# DB_Power-X01.net
KiCad netlist of a schematic drawn in Altium Designer
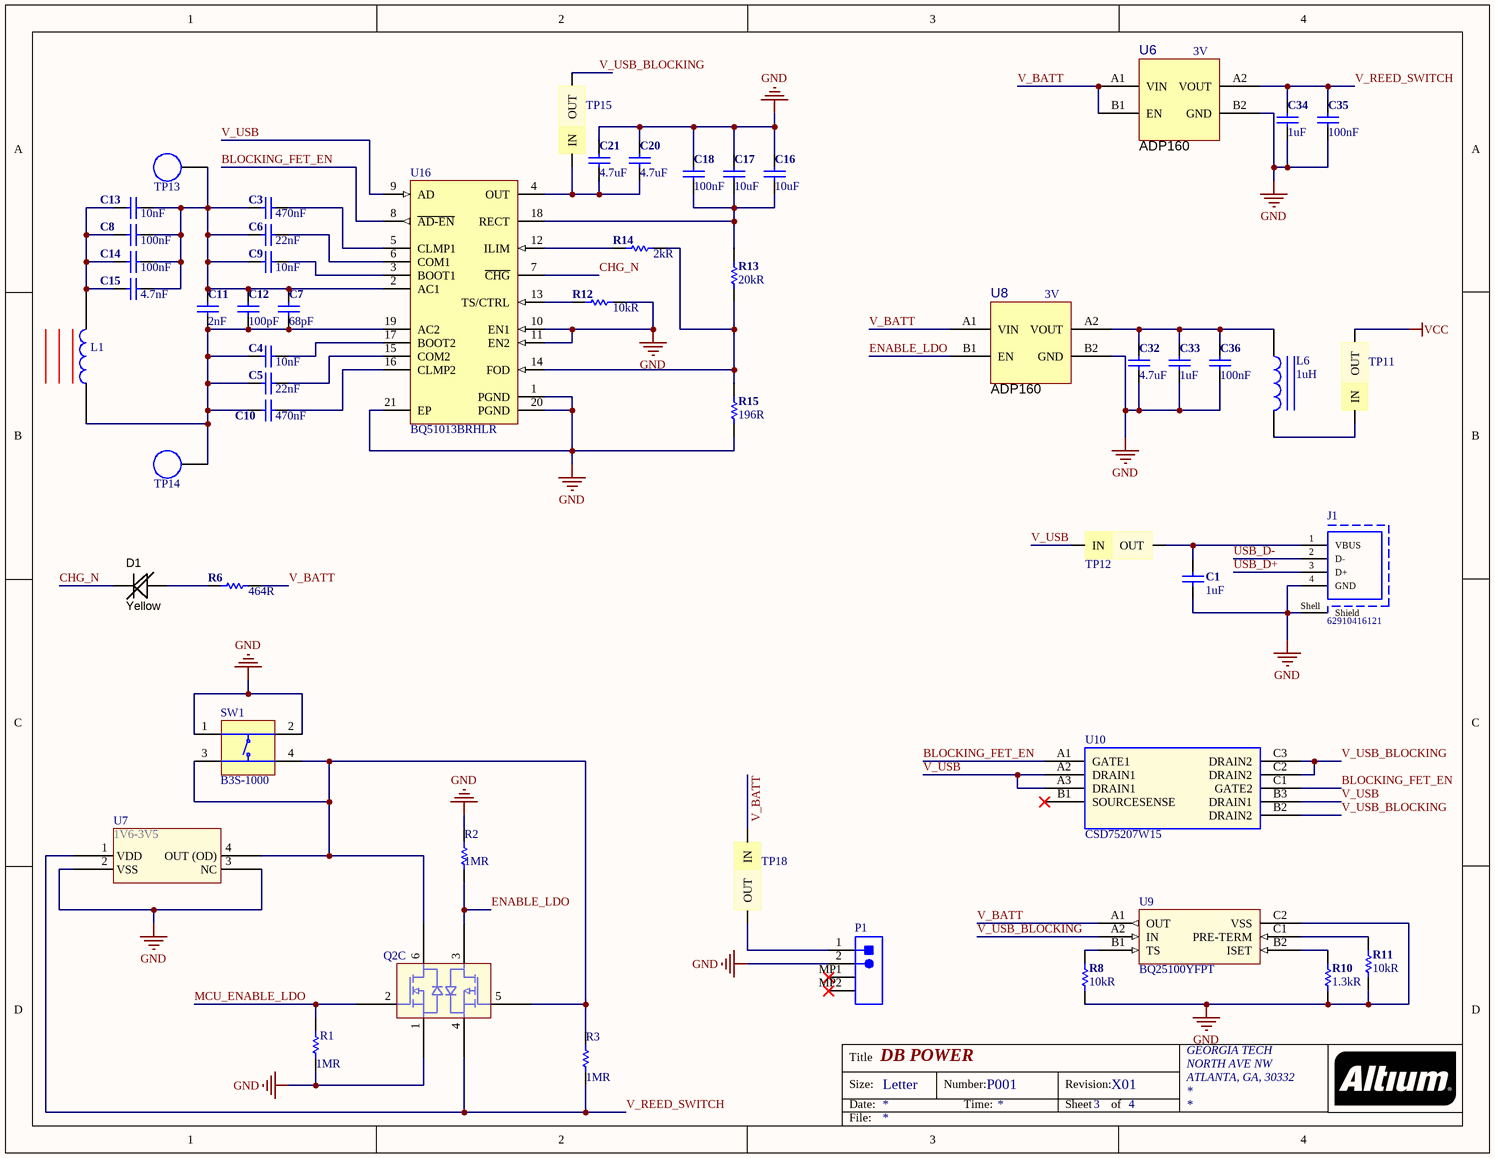
[diagram p0: DB_Power-X01.SchDoc]

(export (version "E")
  (design (tool "Eeschema 10.0.6"))
  (components
    (comp (ref "C1")
      (value "1uF")
      (footprint "C0402")
      (fields
        (field (name "MANUFACTURER") "Yageo")
        (field (name "MANUFACTURER PART NUMBER") "CC0402MRX5R5BB105")
        (field (name "TOLERANCE") "20%")
      )
      (libsource (lib "DB-X01") (part "C-0402(1005)"))
    )
    (comp (ref "C3")
      (value "470nF")
      (footprint "C0402")
      (fields
        (field (name "MANUFACTURER") "Murata")
        (field (name "MANUFACTURER PART NUMBER") "GRT155R61E474ME01D")
        (field (name "TOLERANCE") "20%")
      )
      (libsource (lib "DB-X01") (part "C-0402(1005)"))
    )
    (comp (ref "C4")
      (value "10nF")
      (footprint "C0402")
      (fields
        (field (name "MANUFACTURER") "KEMET")
        (field (name "MANUFACTURER PART NUMBER") "C0402C103J3RACTU")
        (field (name "TOLERANCE") "5%")
      )
      (libsource (lib "DB-X01") (part "C-0402(1005)"))
    )
    (comp (ref "C5")
      (value "22nF")
      (footprint "C0402")
      (fields
        (field (name "MANUFACTURER") "Murata")
        (field (name "MANUFACTURER PART NUMBER") "GRM155R71E223KA61D")
        (field (name "TOLERANCE") "10%")
      )
      (libsource (lib "DB-X01") (part "C-0402(1005)"))
    )
    (comp (ref "C6")
      (value "22nF")
      (footprint "C0402")
      (fields
        (field (name "MANUFACTURER") "Murata")
        (field (name "MANUFACTURER PART NUMBER") "GRM155R71E223KA61D")
        (field (name "TOLERANCE") "10%")
      )
      (libsource (lib "DB-X01") (part "C-0402(1005)"))
    )
    (comp (ref "C7")
      (value "68pF")
      (footprint "C0402")
      (fields
        (field (name "MANUFACTURER") "KEMET")
        (field (name "MANUFACTURER PART NUMBER") "CBR04C680F3GAC")
        (field (name "TOLERANCE") "1%")
      )
      (libsource (lib "DB-X01") (part "C-0402(1005)"))
    )
    (comp (ref "C8")
      (value "100nF")
      (footprint "C0402")
      (fields
        (field (name "MANUFACTURER") "Taiyo Yuden")
        (field (name "MANUFACTURER PART NUMBER") "TMK105BJ104KV-F")
        (field (name "TOLERANCE") "10%")
      )
      (libsource (lib "DB-X01") (part "C-0402(1005)"))
    )
    (comp (ref "C9")
      (value "10nF")
      (footprint "C0402")
      (fields
        (field (name "MANUFACTURER") "KEMET")
        (field (name "MANUFACTURER PART NUMBER") "C0402C103J3RACTU")
        (field (name "TOLERANCE") "5%")
      )
      (libsource (lib "DB-X01") (part "C-0402(1005)"))
    )
    (comp (ref "C10")
      (value "470nF")
      (footprint "C0402")
      (fields
        (field (name "MANUFACTURER") "Murata")
        (field (name "MANUFACTURER PART NUMBER") "GRT155R61E474ME01D")
        (field (name "TOLERANCE") "20%")
      )
      (libsource (lib "DB-X01") (part "C-0402(1005)"))
    )
    (comp (ref "C11")
      (value "2nF")
      (footprint "C0402")
      (fields
        (field (name "MANUFACTURER") "KEMET")
        (field (name "MANUFACTURER PART NUMBER") "C0402C202J3GACTU")
        (field (name "TOLERANCE") "5%")
      )
      (libsource (lib "DB-X01") (part "C-0402(1005)"))
    )
    (comp (ref "C12")
      (value "100pF")
      (footprint "C0402")
      (fields
        (field (name "MANUFACTURER") "KEMET")
        (field (name "MANUFACTURER PART NUMBER") "CBR04C101F3GAC")
        (field (name "TOLERANCE") "1%")
      )
      (libsource (lib "DB-X01") (part "C-0402(1005)"))
    )
    (comp (ref "C13")
      (value "10nF")
      (footprint "C0402")
      (fields
        (field (name "MANUFACTURER") "Yageo")
        (field (name "MANUFACTURER PART NUMBER") "CC0402JRX7R8BB103")
        (field (name "TOLERANCE") "5%")
      )
      (libsource (lib "DB-X01") (part "C-0402(1005)"))
    )
    (comp (ref "C14")
      (value "100nF")
      (footprint "C0402")
      (fields
        (field (name "MANUFACTURER") "Taiyo Yuden")
        (field (name "MANUFACTURER PART NUMBER") "TMK105BJ104KV-F")
        (field (name "TOLERANCE") "10%")
      )
      (libsource (lib "DB-X01") (part "C-0402(1005)"))
    )
    (comp (ref "C15")
      (value "4.7nF")
      (footprint "C0402")
      (fields
        (field (name "MANUFACTURER") "Yageo")
        (field (name "MANUFACTURER PART NUMBER") "CC0402JRX7R8BB472")
        (field (name "TOLERANCE") "5%")
      )
      (libsource (lib "DB-X01") (part "C-0402(1005)"))
    )
    (comp (ref "C16")
      (value "10uF")
      (footprint "C0603")
      (fields
        (field (name "MANUFACTURER") "Murata")
        (field (name "MANUFACTURER PART NUMBER") "GRM188R61E106MA73J")
        (field (name "TOLERANCE") "20%")
      )
      (libsource (lib "DB-X01") (part "C-0603(1608)"))
    )
    (comp (ref "C17")
      (value "10uF")
      (footprint "C0603")
      (fields
        (field (name "MANUFACTURER") "Murata")
        (field (name "MANUFACTURER PART NUMBER") "GRM188R61E106MA73J")
        (field (name "TOLERANCE") "20%")
      )
      (libsource (lib "DB-X01") (part "C-0603(1608)"))
    )
    (comp (ref "C18")
      (value "100nF")
      (footprint "C0603")
      (fields
        (field (name "MANUFACTURER") "Yageo")
        (field (name "MANUFACTURER PART NUMBER") "CC0402ZRY5V8BB104")
        (field (name "TOLERANCE") "80%")
      )
      (libsource (lib "DB-X01") (part "C-0603(1608)"))
    )
    (comp (ref "C20")
      (value "4.7uF")
      (footprint "C0402")
      (description "0402 10 V 4.7 uF ±20% Tolerance X5R Multilayer Ceramic Chip Capacitor")
      (fields
        (field (name "MANUFACTURER") "Murata")
        (field (name "MANUFACTURER PART NUMBER") "GRM155R61A475MEAAD")
      )
      (libsource (lib "DB-X01") (part "C-0402(1005)"))
    )
    (comp (ref "C21")
      (value "4.7uF")
      (footprint "C0402")
      (description "0402 10 V 4.7 uF ±20% Tolerance X5R Multilayer Ceramic Chip Capacitor")
      (fields
        (field (name "MANUFACTURER") "Murata")
        (field (name "MANUFACTURER PART NUMBER") "GRM155R61A475MEAAD")
      )
      (libsource (lib "DB-X01") (part "C-0402(1005)"))
    )
    (comp (ref "C32")
      (value "4.7uF")
      (footprint "C0402")
      (description "0402 10 V 4.7 uF ±20% Tolerance X5R Multilayer Ceramic Chip Capacitor")
      (fields
        (field (name "MANUFACTURER") "Murata")
        (field (name "MANUFACTURER PART NUMBER") "GRM155R61A475MEAAD")
      )
      (libsource (lib "DB-X01") (part "C-0402(1005)"))
    )
    (comp (ref "C33")
      (value "1uF")
      (footprint "C0402")
      (fields
        (field (name "MANUFACTURER") "Yageo")
        (field (name "MANUFACTURER PART NUMBER") "CC0402MRX5R5BB105")
        (field (name "TOLERANCE") "20%")
      )
      (libsource (lib "DB-X01") (part "C-0402(1005)"))
    )
    (comp (ref "C34")
      (value "1uF")
      (footprint "C0402")
      (fields
        (field (name "MANUFACTURER") "Yageo")
        (field (name "MANUFACTURER PART NUMBER") "CC0402MRX5R5BB105")
        (field (name "TOLERANCE") "20%")
      )
      (libsource (lib "DB-X01") (part "C-0402(1005)"))
    )
    (comp (ref "C35")
      (value "100nF")
      (footprint "C0402")
      (fields
        (field (name "MANUFACTURER") "Taiyo Yuden")
        (field (name "MANUFACTURER PART NUMBER") "TMK105BJ104KV-F")
        (field (name "TOLERANCE") "10%")
      )
      (libsource (lib "DB-X01") (part "C-0402(1005)"))
    )
    (comp (ref "C36")
      (value "100nF")
      (footprint "C0402")
      (fields
        (field (name "MANUFACTURER") "Taiyo Yuden")
        (field (name "MANUFACTURER PART NUMBER") "TMK105BJ104KV-F")
        (field (name "TOLERANCE") "10%")
      )
      (libsource (lib "DB-X01") (part "C-0402(1005)"))
    )
    (comp (ref "D1")
      (value "Yellow")
      (footprint "LED_0402")
      (description "Single Color LED, Super Bright Yellow, Water Clear, 0.8mm")
      (fields
        (field (name "MANUFACTURER") "Kingbright")
        (field (name "MANUFACTURER PART NUMBER") "APHHS1005SYCK")
      )
      (libsource (lib "DB-X01") (part "LED_0402(1005)"))
    )
    (comp (ref "J1")
      (value "62910416121")
      (footprint "62910416121")
      (description "USB 2.0 Type B Receptacle WR-COM, Horizontal, SMT, with Pads and Pegs")
      (fields (field (name "MANUFACTURER") "Wurth Electronics"))
      (libsource (lib "Altium Content Vault") (part "WE-USB-4-1SHLD"))
    )
    (comp (ref "L1")
      (value "WIRELESS CHARGING COIL, RECEIVER")
      (footprint "760308101219")
      (description "General Purpose Inductor, 11.8uH, 10%, 1 Element")
      (fields
        (field (name "MANUFACTURER") "Wurth Electronics")
        (field (name "MANUFACTURER PART NUMBER") "760308101219")
      )
      (libsource (lib "DB-X01") (part "WIRELESS_CHARGING_COIL"))
    )
    (comp (ref "L6")
      (value "1uH")
      (footprint "L0402")
      (description "General Purpose Inductor, 1uH, 20%, 1 Element, Ferrite-Core, SMD, 0402")
      (fields
        (field (name "MANUFACTURER") "TDK")
        (field (name "MANUFACTURER PART NUMBER") "MLZ1005M1R0WT000")
      )
      (libsource (lib "DB-X01") (part "Inductor Iron"))
    )
    (comp (ref "P1")
      (value "B2B-PH-SM4-TB(LF)(SN)")
      (footprint "JST-B2B-PH-SM4-TB-2_V")
      (description "Male Header, Pitch 2 mm, 1 x 2 Position, Height 6.6 mm, RoHS, Tape and Reel")
      (fields (field (name "MANUFACTURER") "JST"))
      (libsource (lib "Altium Content Vault") (part "CN-1P-2M-R2"))
    )
    (comp (ref "Q2")
      (value "dual fet SSMini6")
      (footprint "SSMini6-F3-B")
      (fields
        (field (name "MANUFACTURER") "Panasonic")
        (field (name "MANUFACTURER PART NUMBER") "FG6943010R")
      )
      (libsource (lib "DB-X01") (part "FG6943010R"))
    )
    (comp (ref "R1")
      (value "AC0402FR-071ML")
      (footprint "RESC1005X37X25LL05T10")
      (description "100 ohm resistor")
      (fields
        (field (name "MANUFACTURER") "Yageo")
        (field (name "RESISTANCE") "1MR")
        (field (name "TOLERANCE") "1%")
      )
      (libsource (lib "Altium Content Vault") (part "RES"))
    )
    (comp (ref "R2")
      (value "AC0402FR-071ML")
      (footprint "RESC1005X37X25LL05T10")
      (description "100 ohm resistor")
      (fields
        (field (name "MANUFACTURER") "Yageo")
        (field (name "RESISTANCE") "1MR")
        (field (name "TOLERANCE") "1%")
      )
      (libsource (lib "Altium Content Vault") (part "RES"))
    )
    (comp (ref "R3")
      (value "AC0402FR-071ML")
      (footprint "RESC1005X37X25LL05T10")
      (description "100 ohm resistor")
      (fields
        (field (name "MANUFACTURER") "Yageo")
        (field (name "RESISTANCE") "1MR")
        (field (name "TOLERANCE") "1%")
      )
      (libsource (lib "Altium Content Vault") (part "RES"))
    )
    (comp (ref "R6")
      (value "464R")
      (footprint "R0402")
      (fields
        (field (name "MANUFACTURER") "Yageo")
        (field (name "MANUFACTURER PART NUMBER") "RC0402FR-07464RL")
        (field (name "TOLERANCE") "1%")
      )
      (libsource (lib "DB-X01") (part "R-0402(1005)"))
    )
    (comp (ref "R8")
      (value "10kR")
      (footprint "R0402")
      (fields
        (field (name "MANUFACTURER") "Yageo")
        (field (name "MANUFACTURER PART NUMBER") "AC0402FR-0710KL")
        (field (name "TOLERANCE") "1%")
      )
      (libsource (lib "DB-X01") (part "R-0402(1005)"))
    )
    (comp (ref "R10")
      (value "1.3kR")
      (footprint "R0402")
      (fields
        (field (name "MANUFACTURER") "Yageo")
        (field (name "MANUFACTURER PART NUMBER") "RC0402FR-071K3L")
        (field (name "TOLERANCE") "1%")
      )
      (libsource (lib "DB-X01") (part "R-0402(1005)"))
    )
    (comp (ref "R11")
      (value "10kR")
      (footprint "R0402")
      (fields
        (field (name "MANUFACTURER") "Yageo")
        (field (name "MANUFACTURER PART NUMBER") "AC0402FR-0710KL")
        (field (name "TOLERANCE") "1%")
      )
      (libsource (lib "DB-X01") (part "R-0402(1005)"))
    )
    (comp (ref "R12")
      (value "10kR")
      (footprint "R0402")
      (fields
        (field (name "MANUFACTURER") "Yageo")
        (field (name "MANUFACTURER PART NUMBER") "AC0402FR-0710KL")
        (field (name "TOLERANCE") "1%")
      )
      (libsource (lib "DB-X01") (part "R-0402(1005)"))
    )
    (comp (ref "R13")
      (value "20kR")
      (footprint "R0402")
      (fields
        (field (name "MANUFACTURER") "Yageo")
        (field (name "MANUFACTURER PART NUMBER") "AC0402FR-0720KL")
        (field (name "TOLERANCE") "1%")
      )
      (libsource (lib "DB-X01") (part "R-0402(1005)"))
    )
    (comp (ref "R14")
      (value "2kR")
      (footprint "R0402")
      (fields
        (field (name "MANUFACTURER") "Yageo")
        (field (name "MANUFACTURER PART NUMBER") "AC0402FR-072KL")
        (field (name "TOLERANCE") "1%")
      )
      (libsource (lib "DB-X01") (part "R-0402(1005)"))
    )
    (comp (ref "R15")
      (value "196R")
      (footprint "R0402")
      (fields
        (field (name "MANUFACTURER") "Vishay")
        (field (name "MANUFACTURER PART NUMBER") "CRCW0402196RFKED")
        (field (name "TOLERANCE") "1%")
      )
      (libsource (lib "DB-X01") (part "R-0402(1005)"))
    )
    (comp (ref "SW1")
      (value "B3S-1000")
      (footprint "OMRON-B3S-1000-4_V")
      (description "Sealed Tactile Switch, SPST-NO, 3 to 24 V, -25 to 70 degC, 4-Pin SMD, RoHS, Bulk")
      (fields (field (name "MANUFACTURER") "Omron") (field (name "MANUFACTURER PART NUMBER") "B3S-1000P"))
      (libsource (lib "Altium Content Vault") (part "SW-SPST-4_A"))
    )
    (comp (ref "TP11")
      (value "JUMPER")
      (footprint "JUMPER")
      (description "SHUNT LP W/HANDLE 2 POS 30AU")
      (fields
        (field (name "MANUFACTURER") "TE Connectivity")
        (field (name "MANUFACTURER PART NUMBER") "8815452")
      )
      (libsource (lib "DB-X01") (part "JUMPER"))
    )
    (comp (ref "TP12")
      (value "JUMPER")
      (footprint "JUMPER")
      (description "SHUNT LP W/HANDLE 2 POS 30AU")
      (fields
        (field (name "MANUFACTURER") "TE Connectivity")
        (field (name "MANUFACTURER PART NUMBER") "8815452")
      )
      (libsource (lib "") (part "JUMPER_2"))
    )
    (comp (ref "TP13")
      (value "S1751-46R")
      (footprint "S1751-46R")
      (description "PC TEST POINT TIN SMD")
      (fields (field (name "MANUFACTURER") "Harwin Inc."))
      (libsource (lib "DB-X01") (part "S1751-46R"))
    )
    (comp (ref "TP14")
      (value "S1751-46R")
      (footprint "S1751-46R")
      (description "PC TEST POINT TIN SMD")
      (fields (field (name "MANUFACTURER") "Harwin Inc."))
      (libsource (lib "DB-X01") (part "S1751-46R"))
    )
    (comp (ref "TP15")
      (value "JUMPER")
      (footprint "JUMPER")
      (description "SHUNT LP W/HANDLE 2 POS 30AU")
      (fields
        (field (name "MANUFACTURER") "TE Connectivity")
        (field (name "MANUFACTURER PART NUMBER") "8815452")
      )
      (libsource (lib "DB-X01") (part "JUMPER"))
    )
    (comp (ref "TP18")
      (value "JUMPER")
      (footprint "JUMPER")
      (description "SHUNT LP W/HANDLE 2 POS 30AU")
      (fields
        (field (name "MANUFACTURER") "TE Connectivity")
        (field (name "MANUFACTURER PART NUMBER") "8815452")
      )
      (libsource (lib "") (part "JUMPER_1"))
    )
    (comp (ref "U6")
      (value "ADP160")
      (footprint "ADP160")
      (description "Fixed Positive LDO Regulator, 3V, 0.1V Dropout, CMOS, PBGA4")
      (fields
        (field (name "MANUFACTURER") "Analog Devices")
        (field (name "MANUFACTURER PART NUMBER") "ADP172ACBZ-3.0-R7")
        (field (name "OUTPUT VOLTAGE") "3V")
      )
      (libsource (lib "DB-X01") (part "ADP160"))
    )
    (comp (ref "U7")
      (value "S-5712ANSL2-I4T1U")
      (footprint "SNT-4A")
      (description "MAGNETIC SWITCH UNIPOLAR SNT-4A")
      (fields (field (name "MANUFACTURER") "ABLIC U.S.A."))
      (libsource (lib "DB-X01") (part "S-5712ANSL2-I4T1U"))
    )
    (comp (ref "U8")
      (value "ADP160")
      (footprint "ADP160")
      (description "Fixed Positive LDO Regulator, 3V, 0.1V Dropout, CMOS, PBGA4")
      (fields
        (field (name "MANUFACTURER") "Analog Devices")
        (field (name "MANUFACTURER PART NUMBER") "ADP172ACBZ-3.0-R7")
        (field (name "OUTPUT VOLTAGE") "3V")
      )
      (libsource (lib "DB-X01") (part "ADP160"))
    )
    (comp (ref "U9")
      (value "BQ25100YFPT")
      (footprint "YZP0006")
      (description "Power Supply Support Circuit")
      (fields (field (name "MANUFACTURER") "Texas Instruments"))
      (libsource (lib "DB-X01") (part "BQ25100YFPT"))
    )
    (comp (ref "U10")
      (value "CSD75207W15")
      (footprint "YZF0009")
      (description "Small Signal Field-Effect Transistor, P-Channel, Metal-oxide Semiconductor FET")
      (fields (field (name "MANUFACTURER") "Texas Instruments"))
      (libsource (lib "DB-X01") (part "CSD75207W15"))
    )
    (comp (ref "U16")
      (value "BQ51013BRHLR")
      (footprint "BQ51013BRHLR")
      (fields (field (name "MANUFACTURER") "Texas Instruments"))
      (libsource (lib "DB-X01") (part "TI-BQ51013B-RHL20"))
    )
  )
  (nets
    (net (code "1") (name "/BLOCKING_FET_EN") (class "Default")
      (node (ref "U10") (pin "A1") (pinfunction "GATE1_A1") (pintype "passive"))
      (node (ref "U10") (pin "C1") (pinfunction "GATE2_C1") (pintype "passive"))
      (node (ref "U16") (pin "8") (pinfunction "~{AD-EN}_8") (pintype "output"))
    )
    (net (code "2") (name "/CHG_N") (class "Default")
      (node (ref "D1") (pin "K") (pinfunction "K_K") (pintype "passive"))
      (node (ref "U16") (pin "7") (pinfunction "~{CHG}_7") (pintype "open_collector"))
    )
    (net (code "3") (name "/ENABLE_LDO") (class "Default")
      (node (ref "Q2") (pin "3") (pinfunction "D_3") (pintype "passive"))
      (node (ref "R2") (pin "1") (pinfunction "1_1") (pintype "passive"))
      (node (ref "U8") (pin "B1") (pinfunction "EN_B1") (pintype "passive"))
    )
    (net (code "4") (name "/MCU_ENABLE_LDO") (class "Default")
      (node (ref "Q2") (pin "2") (pinfunction "G_2") (pintype "passive"))
      (node (ref "R1") (pin "1") (pinfunction "1_1") (pintype "passive"))
    )
    (net (code "5") (name "/USB_D+") (class "Default")
      (node (ref "J1") (pin "3") (pinfunction "D+_3") (pintype "passive"))
    )
    (net (code "6") (name "/USB_D-") (class "Default")
      (node (ref "J1") (pin "2") (pinfunction "D-_2") (pintype "passive"))
    )
    (net (code "7") (name "/V_BATT") (class "Default")
      (node (ref "R6") (pin "2") (pinfunction "2_2") (pintype "passive"))
      (node (ref "TP18") (pin "1") (pinfunction "IN_1") (pintype "passive"))
      (node (ref "U6") (pin "A1") (pinfunction "VIN_A1") (pintype "passive"))
      (node (ref "U6") (pin "B1") (pinfunction "EN_B1") (pintype "passive"))
      (node (ref "U8") (pin "A1") (pinfunction "VIN_A1") (pintype "passive"))
      (node (ref "U9") (pin "A1") (pinfunction "OUT_A1") (pintype "output"))
    )
    (net (code "8") (name "/V_REED_SWITCH") (class "Default")
      (node (ref "C34") (pin "1") (pinfunction "1_1") (pintype "passive"))
      (node (ref "C35") (pin "2") (pinfunction "2_2") (pintype "passive"))
      (node (ref "Q2") (pin "4") (pinfunction "S_4") (pintype "passive"))
      (node (ref "R3") (pin "1") (pinfunction "1_1") (pintype "passive"))
      (node (ref "U6") (pin "A2") (pinfunction "VOUT_A2") (pintype "passive"))
      (node (ref "U7") (pin "1") (pinfunction "VDD_1") (pintype "passive"))
    )
    (net (code "9") (name "/V_USB") (class "Default")
      (node (ref "TP12") (pin "1") (pinfunction "IN_1") (pintype "passive"))
      (node (ref "U10") (pin "A2") (pinfunction "DRAIN1_A2") (pintype "passive"))
      (node (ref "U10") (pin "A3") (pinfunction "DRAIN1_A3") (pintype "passive"))
      (node (ref "U10") (pin "B3") (pinfunction "DRAIN1_B3") (pintype "passive"))
      (node (ref "U16") (pin "9") (pinfunction "AD_9") (pintype "input"))
    )
    (net (code "10") (name "/V_USB_BLOCKING") (class "Default")
      (node (ref "TP15") (pin "2") (pinfunction "OUT_2") (pintype "passive"))
      (node (ref "U10") (pin "B2") (pinfunction "DRAIN2_B2") (pintype "passive"))
      (node (ref "U10") (pin "C2") (pinfunction "DRAIN2_C2") (pintype "passive"))
      (node (ref "U10") (pin "C3") (pinfunction "DRAIN2_C3") (pintype "passive"))
      (node (ref "U9") (pin "A2") (pinfunction "IN_A2") (pintype "input"))
    )
    (net (code "11") (name "GND") (class "Default")
      (node (ref "C1") (pin "2") (pinfunction "2_2") (pintype "passive"))
      (node (ref "C16") (pin "2") (pinfunction "2_2") (pintype "passive"))
      (node (ref "C17") (pin "2") (pinfunction "2_2") (pintype "passive"))
      (node (ref "C18") (pin "2") (pinfunction "2_2") (pintype "passive"))
      (node (ref "C20") (pin "1") (pinfunction "1_1") (pintype "passive"))
      (node (ref "C21") (pin "1") (pinfunction "1_1") (pintype "passive"))
      (node (ref "C32") (pin "2") (pinfunction "2_2") (pintype "passive"))
      (node (ref "C33") (pin "2") (pinfunction "2_2") (pintype "passive"))
      (node (ref "C34") (pin "2") (pinfunction "2_2") (pintype "passive"))
      (node (ref "C35") (pin "1") (pinfunction "1_1") (pintype "passive"))
      (node (ref "C36") (pin "1") (pinfunction "1_1") (pintype "passive"))
      (node (ref "J1") (pin "4") (pinfunction "GND_4") (pintype "passive"))
      (node (ref "J1") (pin "Shell") (pinfunction "Shield_Shell") (pintype "passive"))
      (node (ref "P1") (pin "2") (pinfunction "2_2") (pintype "passive"))
      (node (ref "Q2") (pin "1") (pinfunction "S_1") (pintype "passive"))
      (node (ref "R1") (pin "2") (pinfunction "2_2") (pintype "passive"))
      (node (ref "R10") (pin "2") (pinfunction "2_2") (pintype "passive"))
      (node (ref "R11") (pin "1") (pinfunction "1_1") (pintype "passive"))
      (node (ref "R12") (pin "2") (pinfunction "2_2") (pintype "passive"))
      (node (ref "R15") (pin "1") (pinfunction "1_1") (pintype "passive"))
      (node (ref "R2") (pin "2") (pinfunction "2_2") (pintype "passive"))
      (node (ref "R8") (pin "1") (pinfunction "1_1") (pintype "passive"))
      (node (ref "SW1") (pin "1") (pinfunction "1_1") (pintype "passive"))
      (node (ref "SW1") (pin "2") (pinfunction "2_2") (pintype "passive"))
      (node (ref "U16") (pin "1") (pinfunction "PGND_1") (pintype "power_in"))
      (node (ref "U16") (pin "10") (pinfunction "EN1_10") (pintype "input"))
      (node (ref "U16") (pin "11") (pinfunction "EN2_11") (pintype "input"))
      (node (ref "U16") (pin "20") (pinfunction "PGND_20") (pintype "power_in"))
      (node (ref "U16") (pin "21") (pinfunction "EP_21") (pintype "passive"))
      (node (ref "U6") (pin "B2") (pinfunction "GND_B2") (pintype "passive"))
      (node (ref "U7") (pin "2") (pinfunction "VSS_2") (pintype "passive"))
      (node (ref "U7") (pin "3") (pinfunction "NC_3") (pintype "passive"))
      (node (ref "U8") (pin "B2") (pinfunction "GND_B2") (pintype "passive"))
      (node (ref "U9") (pin "C2") (pinfunction "VSS_C2") (pintype "power_in"))
    )
    (net (code "12") (name "Net-(C13-Pad1)") (class "Default")
      (node (ref "C13") (pin "1") (pinfunction "1_1") (pintype "passive"))
      (node (ref "C14") (pin "1") (pinfunction "1_1") (pintype "passive"))
      (node (ref "C15") (pin "1") (pinfunction "1_1") (pintype "passive"))
      (node (ref "C8") (pin "1") (pinfunction "1_1") (pintype "passive"))
      (node (ref "L1") (pin "2") (pinfunction "2_2") (pintype "passive"))
    )
    (net (code "13") (name "Net-(D1-PadA)") (class "Default")
      (node (ref "D1") (pin "A") (pinfunction "A_A") (pintype "passive"))
      (node (ref "R6") (pin "1") (pinfunction "1_1") (pintype "passive"))
    )
    (net (code "14") (name "Net-(J1-VBUS)") (class "Default")
      (node (ref "C1") (pin "1") (pinfunction "1_1") (pintype "passive"))
      (node (ref "J1") (pin "1") (pinfunction "VBUS_1") (pintype "passive"))
      (node (ref "TP12") (pin "2") (pinfunction "OUT_2") (pintype "passive"))
    )
    (net (code "15") (name "Net-(TP11-IN)") (class "Default")
      (node (ref "L6") (pin "2") (pinfunction "2_2") (pintype "passive"))
      (node (ref "TP11") (pin "1") (pinfunction "IN_1") (pintype "passive"))
    )
    (net (code "16") (name "Net-(TP15-IN)") (class "Default")
      (node (ref "C20") (pin "2") (pinfunction "2_2") (pintype "passive"))
      (node (ref "C21") (pin "2") (pinfunction "2_2") (pintype "passive"))
      (node (ref "TP15") (pin "1") (pinfunction "IN_1") (pintype "passive"))
      (node (ref "U16") (pin "4") (pinfunction "OUT_4") (pintype "power_in"))
    )
    (net (code "17") (name "Net-(TP18-OUT)") (class "Default")
      (node (ref "P1") (pin "1") (pinfunction "1_1") (pintype "passive"))
      (node (ref "TP18") (pin "2") (pinfunction "OUT_2") (pintype "passive"))
    )
    (net (code "18") (name "Net-(U7-OUT_(OD))") (class "Default")
      (node (ref "Q2") (pin "5") (pinfunction "G_5") (pintype "passive"))
      (node (ref "Q2") (pin "6") (pinfunction "D_6") (pintype "passive"))
      (node (ref "R3") (pin "2") (pinfunction "2_2") (pintype "passive"))
      (node (ref "SW1") (pin "3") (pinfunction "3_3") (pintype "passive"))
      (node (ref "SW1") (pin "4") (pinfunction "4_4") (pintype "passive"))
      (node (ref "U7") (pin "4") (pinfunction "OUT_(OD)_4") (pintype "passive"))
    )
    (net (code "19") (name "Net-(U8-VOUT)") (class "Default")
      (node (ref "C32") (pin "1") (pinfunction "1_1") (pintype "passive"))
      (node (ref "C33") (pin "1") (pinfunction "1_1") (pintype "passive"))
      (node (ref "C36") (pin "2") (pinfunction "2_2") (pintype "passive"))
      (node (ref "L6") (pin "1") (pinfunction "1_1") (pintype "passive"))
      (node (ref "U8") (pin "A2") (pinfunction "VOUT_A2") (pintype "passive"))
    )
    (net (code "20") (name "Net-(U9-ISET)") (class "Default")
      (node (ref "R10") (pin "1") (pinfunction "1_1") (pintype "passive"))
      (node (ref "U9") (pin "B2") (pinfunction "ISET_B2") (pintype "input"))
    )
    (net (code "21") (name "Net-(U9-PRE-TERM)") (class "Default")
      (node (ref "R11") (pin "2") (pinfunction "2_2") (pintype "passive"))
      (node (ref "U9") (pin "C1") (pinfunction "PRE-TERM_C1") (pintype "input"))
    )
    (net (code "22") (name "Net-(U9-TS)") (class "Default")
      (node (ref "R8") (pin "2") (pinfunction "2_2") (pintype "passive"))
      (node (ref "U9") (pin "B1") (pinfunction "TS_B1") (pintype "input"))
    )
    (net (code "23") (name "Net-(U16-AC1)") (class "Default")
      (node (ref "C11") (pin "1") (pinfunction "1_1") (pintype "passive"))
      (node (ref "C12") (pin "1") (pinfunction "1_1") (pintype "passive"))
      (node (ref "C13") (pin "2") (pinfunction "2_2") (pintype "passive"))
      (node (ref "C14") (pin "2") (pinfunction "2_2") (pintype "passive"))
      (node (ref "C15") (pin "2") (pinfunction "2_2") (pintype "passive"))
      (node (ref "C3") (pin "1") (pinfunction "1_1") (pintype "passive"))
      (node (ref "C6") (pin "1") (pinfunction "1_1") (pintype "passive"))
      (node (ref "C7") (pin "1") (pinfunction "1_1") (pintype "passive"))
      (node (ref "C8") (pin "2") (pinfunction "2_2") (pintype "passive"))
      (node (ref "C9") (pin "1") (pinfunction "1_1") (pintype "passive"))
      (node (ref "TP13") (pin "1") (pinfunction "1_1") (pintype "passive"))
      (node (ref "U16") (pin "2") (pinfunction "AC1_2") (pintype "power_in"))
    )
    (net (code "24") (name "Net-(U16-AC2)") (class "Default")
      (node (ref "C10") (pin "1") (pinfunction "1_1") (pintype "passive"))
      (node (ref "C11") (pin "2") (pinfunction "2_2") (pintype "passive"))
      (node (ref "C12") (pin "2") (pinfunction "2_2") (pintype "passive"))
      (node (ref "C4") (pin "1") (pinfunction "1_1") (pintype "passive"))
      (node (ref "C5") (pin "1") (pinfunction "1_1") (pintype "passive"))
      (node (ref "C7") (pin "2") (pinfunction "2_2") (pintype "passive"))
      (node (ref "L1") (pin "1") (pinfunction "1_1") (pintype "passive"))
      (node (ref "TP14") (pin "1") (pinfunction "1_1") (pintype "passive"))
      (node (ref "U16") (pin "19") (pinfunction "AC2_19") (pintype "power_in"))
    )
    (net (code "25") (name "Net-(U16-BOOT1)") (class "Default")
      (node (ref "C9") (pin "2") (pinfunction "2_2") (pintype "passive"))
      (node (ref "U16") (pin "3") (pinfunction "BOOT1_3") (pintype "passive"))
    )
    (net (code "26") (name "Net-(U16-BOOT2)") (class "Default")
      (node (ref "C4") (pin "2") (pinfunction "2_2") (pintype "passive"))
      (node (ref "U16") (pin "17") (pinfunction "BOOT2_17") (pintype "passive"))
    )
    (net (code "27") (name "Net-(U16-CLMP1)") (class "Default")
      (node (ref "C3") (pin "2") (pinfunction "2_2") (pintype "passive"))
      (node (ref "U16") (pin "5") (pinfunction "CLMP1_5") (pintype "open_collector"))
    )
    (net (code "28") (name "Net-(U16-CLMP2)") (class "Default")
      (node (ref "C10") (pin "2") (pinfunction "2_2") (pintype "passive"))
      (node (ref "U16") (pin "16") (pinfunction "CLMP2_16") (pintype "open_collector"))
    )
    (net (code "29") (name "Net-(U16-COM1)") (class "Default")
      (node (ref "C6") (pin "2") (pinfunction "2_2") (pintype "passive"))
      (node (ref "U16") (pin "6") (pinfunction "COM1_6") (pintype "open_collector"))
    )
    (net (code "30") (name "Net-(U16-COM2)") (class "Default")
      (node (ref "C5") (pin "2") (pinfunction "2_2") (pintype "passive"))
      (node (ref "U16") (pin "15") (pinfunction "COM2_15") (pintype "open_collector"))
    )
    (net (code "31") (name "Net-(U16-FOD)") (class "Default")
      (node (ref "R13") (pin "2") (pinfunction "2_2") (pintype "passive"))
      (node (ref "R14") (pin "2") (pinfunction "2_2") (pintype "passive"))
      (node (ref "R15") (pin "2") (pinfunction "2_2") (pintype "passive"))
      (node (ref "U16") (pin "14") (pinfunction "FOD_14") (pintype "input"))
    )
    (net (code "32") (name "Net-(U16-ILIM)") (class "Default")
      (node (ref "R14") (pin "1") (pinfunction "1_1") (pintype "passive"))
      (node (ref "U16") (pin "12") (pinfunction "ILIM_12") (pintype "input"))
    )
    (net (code "33") (name "Net-(U16-RECT)") (class "Default")
      (node (ref "C16") (pin "1") (pinfunction "1_1") (pintype "passive"))
      (node (ref "C17") (pin "1") (pinfunction "1_1") (pintype "passive"))
      (node (ref "C18") (pin "1") (pinfunction "1_1") (pintype "passive"))
      (node (ref "R13") (pin "1") (pinfunction "1_1") (pintype "passive"))
      (node (ref "U16") (pin "18") (pinfunction "RECT_18") (pintype "passive"))
    )
    (net (code "34") (name "Net-(U16-TS{slash}CTRL)") (class "Default")
      (node (ref "R12") (pin "1") (pinfunction "1_1") (pintype "passive"))
      (node (ref "U16") (pin "13") (pinfunction "TS/CTRL_13") (pintype "input"))
    )
    (net (code "35") (name "VCC") (class "Default")
      (node (ref "TP11") (pin "2") (pinfunction "OUT_2") (pintype "passive"))
    )
    (net (code "36") (name "unconnected-(P1-PadMP1)") (class "Default")
      (node (ref "P1") (pin "MP1") (pinfunction "MP1_MP1") (pintype "passive+no_connect"))
    )
    (net (code "37") (name "unconnected-(P1-PadMP2)") (class "Default")
      (node (ref "P1") (pin "MP2") (pinfunction "MP2_MP2") (pintype "passive+no_connect"))
    )
    (net (code "38") (name "unconnected-(U10-SOURCESENSE-PadB1)") (class "Default")
      (node (ref "U10") (pin "B1") (pinfunction "SOURCESENSE_B1") (pintype "passive+no_connect"))
    )
  )
)
